# sequencer.net
KiCad netlist of a schematic drawn in EAGLE
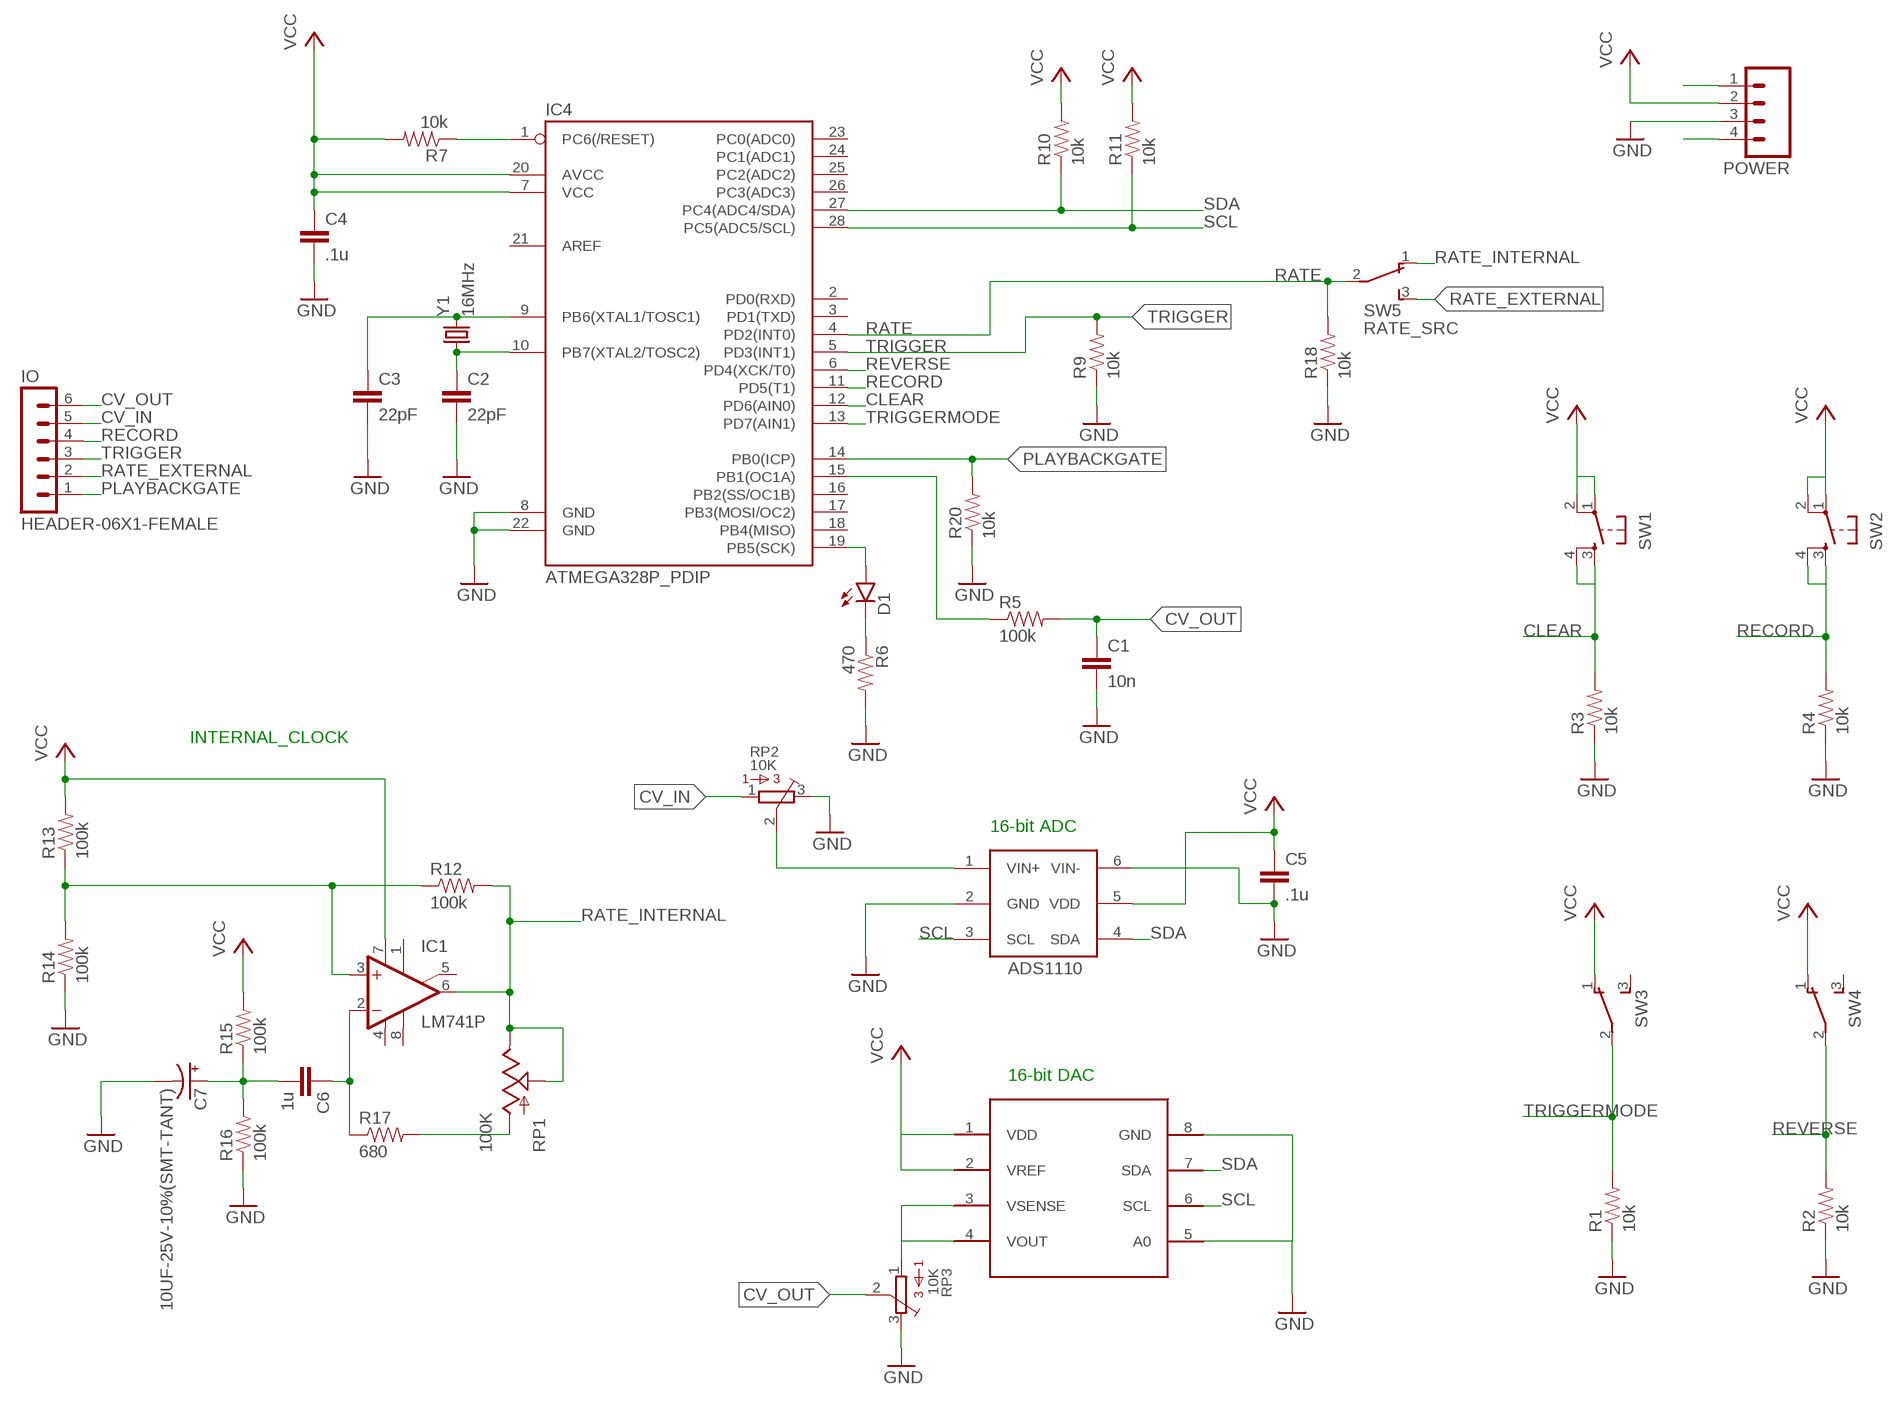
[diagram p0: schematic, sheet 1]

(export (version "E")
  (design (tool "Eeschema 10.0.6"))
  (components
    (comp (ref "C1")
      (value "10n")
      (footprint "eagle-import:1206")
      (libsource (lib "eagle-import") (part "CAP1206"))
    )
    (comp (ref "C2")
      (value "22pF")
      (footprint "eagle-import:1206")
      (libsource (lib "eagle-import") (part "CAP1206"))
    )
    (comp (ref "C3")
      (value "22pF")
      (footprint "eagle-import:1206")
      (libsource (lib "eagle-import") (part "CAP1206"))
    )
    (comp (ref "C4")
      (value ".1u")
      (footprint "eagle-import:1206")
      (libsource (lib "eagle-import") (part "CAP1206"))
    )
    (comp (ref "C5")
      (value ".1u")
      (footprint "eagle-import:1206")
      (libsource (lib "eagle-import") (part "CAP1206"))
    )
    (comp (ref "C6")
      (value "1u")
      (footprint "eagle-import:1206")
      (libsource (lib "eagle-import") (part "CAP1206"))
    )
    (comp (ref "C7")
      (value "10UF-25V-10%(SMT-TANT)")
      (footprint "eagle-import:EIA6032-NOM")
      (libsource (lib "eagle-import") (part "10UF-25V-10%(SMT-TANT)"))
    )
    (comp (ref "D1")
      (value "LED-3MM-NO_SILK")
      (footprint "eagle-import:LED3MM-NS")
      (libsource (lib "eagle-import") (part "LED-3MM-NO_SILK"))
    )
    (comp (ref "IC1")
      (value "LM741P")
      (footprint "eagle-import:DIL08")
      (libsource (lib "eagle-import") (part "741PLM"))
    )
    (comp (ref "IC2")
      (value "ADS1110")
      (footprint "eagle-import:SOT-23-6")
      (libsource (lib "eagle-import") (part "ADS1110"))
    )
    (comp (ref "IC3")
      (value "DAC8571")
      (footprint "eagle-import:8MSOP")
      (libsource (lib "eagle-import") (part "DAC8571"))
    )
    (comp (ref "IC4")
      (value "ATMEGA328P_PDIP")
      (footprint "eagle-import:DIL28-3")
      (libsource (lib "eagle-import") (part "ATMEGA328P_PDIP"))
    )
    (comp (ref "IO")
      (value "HEADER-06X1-FEMALE")
      (footprint "eagle-import:06X1-PTH")
      (libsource (lib "eagle-import") (part "HEADER-06X1?-FEMALE"))
    )
    (comp (ref "POWER")
      (value "M04PTH")
      (footprint "eagle-import:1X04")
      (libsource (lib "eagle-import") (part "M04PTH"))
    )
    (comp (ref "R1")
      (value "10k")
      (footprint "eagle-import:1206")
      (libsource (lib "eagle-import") (part "RESISTOR1206"))
    )
    (comp (ref "R2")
      (value "10k")
      (footprint "eagle-import:1206")
      (libsource (lib "eagle-import") (part "RESISTOR1206"))
    )
    (comp (ref "R3")
      (value "10k")
      (footprint "eagle-import:1206")
      (libsource (lib "eagle-import") (part "RESISTOR1206"))
    )
    (comp (ref "R4")
      (value "10k")
      (footprint "eagle-import:1206")
      (libsource (lib "eagle-import") (part "RESISTOR1206"))
    )
    (comp (ref "R5")
      (value "100k")
      (footprint "eagle-import:1206")
      (libsource (lib "eagle-import") (part "RESISTOR1206"))
    )
    (comp (ref "R6")
      (value "470")
      (footprint "eagle-import:1206")
      (libsource (lib "eagle-import") (part "RESISTOR1206"))
    )
    (comp (ref "R7")
      (value "10k")
      (footprint "eagle-import:1206")
      (libsource (lib "eagle-import") (part "RESISTOR1206"))
    )
    (comp (ref "R9")
      (value "10k")
      (footprint "eagle-import:1206")
      (libsource (lib "eagle-import") (part "RESISTOR1206"))
    )
    (comp (ref "R10")
      (value "10k")
      (footprint "eagle-import:1206")
      (libsource (lib "eagle-import") (part "RESISTOR1206"))
    )
    (comp (ref "R11")
      (value "10k")
      (footprint "eagle-import:1206")
      (libsource (lib "eagle-import") (part "RESISTOR1206"))
    )
    (comp (ref "R12")
      (value "100k")
      (footprint "eagle-import:1206")
      (libsource (lib "eagle-import") (part "RESISTOR1206"))
    )
    (comp (ref "R13")
      (value "100k")
      (footprint "eagle-import:1206")
      (libsource (lib "eagle-import") (part "RESISTOR1206"))
    )
    (comp (ref "R14")
      (value "100k")
      (footprint "eagle-import:1206")
      (libsource (lib "eagle-import") (part "RESISTOR1206"))
    )
    (comp (ref "R15")
      (value "100k")
      (footprint "eagle-import:1206")
      (libsource (lib "eagle-import") (part "RESISTOR1206"))
    )
    (comp (ref "R16")
      (value "100k")
      (footprint "eagle-import:1206")
      (libsource (lib "eagle-import") (part "RESISTOR1206"))
    )
    (comp (ref "R17")
      (value "680")
      (footprint "eagle-import:1206")
      (libsource (lib "eagle-import") (part "RESISTOR1206"))
    )
    (comp (ref "R18")
      (value "10k")
      (footprint "eagle-import:1206")
      (libsource (lib "eagle-import") (part "RESISTOR1206"))
    )
    (comp (ref "R20")
      (value "10k")
      (footprint "eagle-import:1206")
      (libsource (lib "eagle-import") (part "RESISTOR1206"))
    )
    (comp (ref "RP1")
      (value "100K")
      (footprint "eagle-import:ALPS_POT_KIT")
      (libsource (lib "eagle-import") (part "POTALPS-KIT"))
    )
    (comp (ref "RP2")
      (value "10K")
      (footprint "eagle-import:3386P")
      (libsource (lib "eagle-import") (part "3386-P"))
    )
    (comp (ref "RP3")
      (value "10K")
      (footprint "eagle-import:3386P")
      (libsource (lib "eagle-import") (part "3386-P"))
    )
    (comp (ref "SW1")
      (value "TAC_SWITCHPTH")
      (footprint "eagle-import:TACTILE-PTH")
      (libsource (lib "eagle-import") (part "TAC_SWITCHPTH"))
    )
    (comp (ref "SW2")
      (value "TAC_SWITCHPTH")
      (footprint "eagle-import:TACTILE-PTH")
      (libsource (lib "eagle-import") (part "TAC_SWITCHPTH"))
    )
    (comp (ref "SW3")
      (value "TL36YO")
      (footprint "eagle-import:TL3XYO")
      (libsource (lib "eagle-import") (part "TL36YO"))
    )
    (comp (ref "SW4")
      (value "TL36YO")
      (footprint "eagle-import:TL3XYO")
      (libsource (lib "eagle-import") (part "TL36YO"))
    )
    (comp (ref "SW5")
      (value "RATE_SRC")
      (footprint "eagle-import:TL3XYO")
      (libsource (lib "eagle-import") (part "TL36YO"))
    )
    (comp (ref "Y1")
      (value "16MHz")
      (footprint "eagle-import:HC49US")
      (libsource (lib "eagle-import") (part "CRYSTALHC49US"))
    )
  )
  (nets
    (net (code "1") (name "/CLEAR") (class "Default")
      (node (ref "IC4") (pin "12") (pinfunction "PD6(AIN0)_12") (pintype "bidirectional"))
      (node (ref "R3") (pin "2") (pinfunction "2_2") (pintype "passive"))
      (node (ref "SW1") (pin "3") (pinfunction "3_3") (pintype "passive"))
      (node (ref "SW1") (pin "4") (pinfunction "4_4") (pintype "passive"))
    )
    (net (code "2") (name "/RATE") (class "Default")
      (node (ref "IC4") (pin "4") (pinfunction "PD2(INT0)_4") (pintype "bidirectional"))
      (node (ref "R18") (pin "2") (pinfunction "2_2") (pintype "passive"))
      (node (ref "SW5") (pin "2") (pinfunction "P_2") (pintype "passive"))
    )
    (net (code "3") (name "/RATE_INTERNAL") (class "Default")
      (node (ref "IC1") (pin "6") (pinfunction "OUT_6") (pintype "output"))
      (node (ref "R12") (pin "2") (pinfunction "2_2") (pintype "passive"))
      (node (ref "RP1") (pin "P$1") (pinfunction "E_P$1") (pintype "passive"))
      (node (ref "RP1") (pin "P$2") (pinfunction "S_P$2") (pintype "passive"))
      (node (ref "SW5") (pin "1") (pinfunction "O_1") (pintype "passive"))
    )
    (net (code "4") (name "/RECORD") (class "Default")
      (node (ref "IC4") (pin "11") (pinfunction "PD5(T1)_11") (pintype "bidirectional"))
      (node (ref "IO") (pin "4") (pinfunction "4_4") (pintype "passive"))
      (node (ref "R4") (pin "2") (pinfunction "2_2") (pintype "passive"))
      (node (ref "SW2") (pin "3") (pinfunction "3_3") (pintype "passive"))
      (node (ref "SW2") (pin "4") (pinfunction "4_4") (pintype "passive"))
    )
    (net (code "5") (name "/REVERSE") (class "Default")
      (node (ref "IC4") (pin "6") (pinfunction "PD4(XCK/T0)_6") (pintype "bidirectional"))
      (node (ref "R2") (pin "2") (pinfunction "2_2") (pintype "passive"))
      (node (ref "SW4") (pin "2") (pinfunction "P_2") (pintype "passive"))
    )
    (net (code "6") (name "/SCL") (class "Default")
      (node (ref "IC2") (pin "3") (pinfunction "SCL_3") (pintype "bidirectional"))
      (node (ref "IC3") (pin "6") (pinfunction "SCL_6") (pintype "bidirectional"))
      (node (ref "IC4") (pin "28") (pinfunction "PC5(ADC5/SCL)_28") (pintype "bidirectional"))
      (node (ref "R11") (pin "1") (pinfunction "1_1") (pintype "passive"))
    )
    (net (code "7") (name "/SDA") (class "Default")
      (node (ref "IC2") (pin "4") (pinfunction "SDA_4") (pintype "bidirectional"))
      (node (ref "IC3") (pin "7") (pinfunction "SDA_7") (pintype "bidirectional"))
      (node (ref "IC4") (pin "27") (pinfunction "PC4(ADC4/SDA)_27") (pintype "bidirectional"))
      (node (ref "R10") (pin "1") (pinfunction "1_1") (pintype "passive"))
    )
    (net (code "8") (name "/TRIGGERMODE") (class "Default")
      (node (ref "IC4") (pin "13") (pinfunction "PD7(AIN1)_13") (pintype "bidirectional"))
      (node (ref "R1") (pin "2") (pinfunction "2_2") (pintype "passive"))
      (node (ref "SW3") (pin "2") (pinfunction "P_2") (pintype "passive"))
    )
    (net (code "9") (name "/V-") (class "Default")
      (node (ref "IC1") (pin "4") (pinfunction "V-_4") (pintype "power_in"))
    )
    (net (code "10") (name "CV_IN") (class "Default")
      (node (ref "IO") (pin "5") (pinfunction "5_5") (pintype "passive"))
      (node (ref "RP2") (pin "1") (pinfunction "1_1") (pintype "passive"))
    )
    (net (code "11") (name "CV_OUT") (class "Default")
      (node (ref "C1") (pin "1") (pinfunction "1_1") (pintype "passive"))
      (node (ref "IO") (pin "6") (pinfunction "6_6") (pintype "passive"))
      (node (ref "R5") (pin "2") (pinfunction "2_2") (pintype "passive"))
      (node (ref "RP3") (pin "2") (pinfunction "2_2") (pintype "passive"))
    )
    (net (code "12") (name "GND") (class "Default")
      (node (ref "C1") (pin "2") (pinfunction "2_2") (pintype "passive"))
      (node (ref "C2") (pin "2") (pinfunction "2_2") (pintype "passive"))
      (node (ref "C3") (pin "2") (pinfunction "2_2") (pintype "passive"))
      (node (ref "C4") (pin "2") (pinfunction "2_2") (pintype "passive"))
      (node (ref "C5") (pin "2") (pinfunction "2_2") (pintype "passive"))
      (node (ref "C7") (pin "C") (pinfunction "-_C") (pintype "passive"))
      (node (ref "IC2") (pin "2") (pinfunction "GND_2") (pintype "bidirectional"))
      (node (ref "IC2") (pin "6") (pinfunction "VIN-_6") (pintype "bidirectional"))
      (node (ref "IC3") (pin "5") (pinfunction "A0_5") (pintype "bidirectional"))
      (node (ref "IC3") (pin "8") (pinfunction "GND_8") (pintype "bidirectional"))
      (node (ref "IC4") (pin "22") (pinfunction "GND_22") (pintype "bidirectional"))
      (node (ref "IC4") (pin "8") (pinfunction "GND_8") (pintype "bidirectional"))
      (node (ref "POWER") (pin "3") (pinfunction "3_3") (pintype "passive"))
      (node (ref "R1") (pin "1") (pinfunction "1_1") (pintype "passive"))
      (node (ref "R14") (pin "1") (pinfunction "1_1") (pintype "passive"))
      (node (ref "R16") (pin "1") (pinfunction "1_1") (pintype "passive"))
      (node (ref "R18") (pin "1") (pinfunction "1_1") (pintype "passive"))
      (node (ref "R2") (pin "1") (pinfunction "1_1") (pintype "passive"))
      (node (ref "R20") (pin "1") (pinfunction "1_1") (pintype "passive"))
      (node (ref "R3") (pin "1") (pinfunction "1_1") (pintype "passive"))
      (node (ref "R4") (pin "1") (pinfunction "1_1") (pintype "passive"))
      (node (ref "R6") (pin "2") (pinfunction "2_2") (pintype "passive"))
      (node (ref "R9") (pin "1") (pinfunction "1_1") (pintype "passive"))
      (node (ref "RP2") (pin "3") (pinfunction "3_3") (pintype "passive"))
      (node (ref "RP3") (pin "3") (pinfunction "3_3") (pintype "passive"))
    )
    (net (code "13") (name "Net-(C7-+)") (class "Default")
      (node (ref "C6") (pin "2") (pinfunction "2_2") (pintype "passive"))
      (node (ref "C7") (pin "A") (pinfunction "+_A") (pintype "passive"))
      (node (ref "R15") (pin "1") (pinfunction "1_1") (pintype "passive"))
      (node (ref "R16") (pin "2") (pinfunction "2_2") (pintype "passive"))
    )
    (net (code "14") (name "Net-(D1-C)") (class "Default")
      (node (ref "D1") (pin "K") (pinfunction "C_K") (pintype "passive"))
      (node (ref "R6") (pin "1") (pinfunction "1_1") (pintype "passive"))
    )
    (net (code "15") (name "Net-(IC1-+IN)") (class "Default")
      (node (ref "IC1") (pin "3") (pinfunction "+IN_3") (pintype "input"))
      (node (ref "R12") (pin "1") (pinfunction "1_1") (pintype "passive"))
      (node (ref "R13") (pin "1") (pinfunction "1_1") (pintype "passive"))
      (node (ref "R14") (pin "2") (pinfunction "2_2") (pintype "passive"))
    )
    (net (code "16") (name "Net-(IC1--IN)") (class "Default")
      (node (ref "C6") (pin "1") (pinfunction "1_1") (pintype "passive"))
      (node (ref "IC1") (pin "2") (pinfunction "-IN_2") (pintype "input"))
      (node (ref "R17") (pin "1") (pinfunction "1_1") (pintype "passive"))
    )
    (net (code "17") (name "Net-(IC2-VIN+)") (class "Default")
      (node (ref "IC2") (pin "1") (pinfunction "VIN+_1") (pintype "bidirectional"))
      (node (ref "RP2") (pin "2") (pinfunction "2_2") (pintype "passive"))
    )
    (net (code "18") (name "Net-(IC3-VOUT)") (class "Default")
      (node (ref "IC3") (pin "3") (pinfunction "VSENSE_3") (pintype "bidirectional"))
      (node (ref "IC3") (pin "4") (pinfunction "VOUT_4") (pintype "bidirectional"))
      (node (ref "RP3") (pin "1") (pinfunction "1_1") (pintype "passive"))
    )
    (net (code "19") (name "Net-(IC4-PB1(OC1A))") (class "Default")
      (node (ref "IC4") (pin "15") (pinfunction "PB1(OC1A)_15") (pintype "bidirectional"))
      (node (ref "R5") (pin "1") (pinfunction "1_1") (pintype "passive"))
    )
    (net (code "20") (name "Net-(IC4-PB5(SCK))") (class "Default")
      (node (ref "D1") (pin "A") (pinfunction "A_A") (pintype "passive"))
      (node (ref "IC4") (pin "19") (pinfunction "PB5(SCK)_19") (pintype "bidirectional"))
    )
    (net (code "21") (name "Net-(IC4-PB6(XTAL1{slash}TOSC1))") (class "Default")
      (node (ref "C3") (pin "1") (pinfunction "1_1") (pintype "passive"))
      (node (ref "IC4") (pin "9") (pinfunction "PB6(XTAL1/TOSC1)_9") (pintype "bidirectional"))
      (node (ref "Y1") (pin "2") (pinfunction "2_2") (pintype "passive"))
    )
    (net (code "22") (name "Net-(IC4-PB7(XTAL2{slash}TOSC2))") (class "Default")
      (node (ref "C2") (pin "1") (pinfunction "1_1") (pintype "passive"))
      (node (ref "IC4") (pin "10") (pinfunction "PB7(XTAL2/TOSC2)_10") (pintype "bidirectional"))
      (node (ref "Y1") (pin "1") (pinfunction "1_1") (pintype "passive"))
    )
    (net (code "23") (name "Net-(IC4-PC6({slash}RESET))") (class "Default")
      (node (ref "IC4") (pin "1") (pinfunction "PC6(/RESET)_1") (pintype "bidirectional"))
      (node (ref "R7") (pin "1") (pinfunction "1_1") (pintype "passive"))
    )
    (net (code "24") (name "Net-(RP1-A)") (class "Default")
      (node (ref "R17") (pin "2") (pinfunction "2_2") (pintype "passive"))
      (node (ref "RP1") (pin "P$3") (pinfunction "A_P$3") (pintype "passive"))
    )
    (net (code "25") (name "PLAYBACKGATE") (class "Default")
      (node (ref "IC4") (pin "14") (pinfunction "PB0(ICP)_14") (pintype "bidirectional"))
      (node (ref "IO") (pin "1") (pinfunction "1_1") (pintype "passive"))
      (node (ref "R20") (pin "2") (pinfunction "2_2") (pintype "passive"))
    )
    (net (code "26") (name "RATE_EXTERNAL") (class "Default")
      (node (ref "IO") (pin "2") (pinfunction "2_2") (pintype "passive"))
      (node (ref "SW5") (pin "3") (pinfunction "S_3") (pintype "passive"))
    )
    (net (code "27") (name "TRIGGER") (class "Default")
      (node (ref "IC4") (pin "5") (pinfunction "PD3(INT1)_5") (pintype "bidirectional"))
      (node (ref "IO") (pin "3") (pinfunction "3_3") (pintype "passive"))
      (node (ref "R9") (pin "2") (pinfunction "2_2") (pintype "passive"))
    )
    (net (code "28") (name "VCC") (class "Default")
      (node (ref "C4") (pin "1") (pinfunction "1_1") (pintype "passive"))
      (node (ref "C5") (pin "1") (pinfunction "1_1") (pintype "passive"))
      (node (ref "IC1") (pin "7") (pinfunction "V+_7") (pintype "power_in"))
      (node (ref "IC2") (pin "5") (pinfunction "VDD_5") (pintype "bidirectional"))
      (node (ref "IC3") (pin "1") (pinfunction "VDD_1") (pintype "bidirectional"))
      (node (ref "IC3") (pin "2") (pinfunction "VREF_2") (pintype "bidirectional"))
      (node (ref "IC4") (pin "20") (pinfunction "AVCC_20") (pintype "bidirectional"))
      (node (ref "IC4") (pin "7") (pinfunction "VCC_7") (pintype "bidirectional"))
      (node (ref "POWER") (pin "2") (pinfunction "2_2") (pintype "passive"))
      (node (ref "R10") (pin "2") (pinfunction "2_2") (pintype "passive"))
      (node (ref "R11") (pin "2") (pinfunction "2_2") (pintype "passive"))
      (node (ref "R13") (pin "2") (pinfunction "2_2") (pintype "passive"))
      (node (ref "R15") (pin "2") (pinfunction "2_2") (pintype "passive"))
      (node (ref "R7") (pin "2") (pinfunction "2_2") (pintype "passive"))
      (node (ref "SW1") (pin "1") (pinfunction "1_1") (pintype "passive"))
      (node (ref "SW1") (pin "2") (pinfunction "2_2") (pintype "passive"))
      (node (ref "SW2") (pin "1") (pinfunction "1_1") (pintype "passive"))
      (node (ref "SW2") (pin "2") (pinfunction "2_2") (pintype "passive"))
      (node (ref "SW3") (pin "1") (pinfunction "O_1") (pintype "passive"))
      (node (ref "SW4") (pin "1") (pinfunction "O_1") (pintype "passive"))
    )
    (net (code "29") (name "unconnected-(IC1-ON1-Pad1)") (class "Default")
      (node (ref "IC1") (pin "1") (pinfunction "ON1_1") (pintype "passive"))
    )
    (net (code "30") (name "unconnected-(IC1-ON2-Pad5)") (class "Default")
      (node (ref "IC1") (pin "5") (pinfunction "ON2_5") (pintype "passive"))
    )
    (net (code "31") (name "unconnected-(IC1-OPT-Pad8)") (class "Default")
      (node (ref "IC1") (pin "8") (pinfunction "OPT_8") (pintype "passive"))
    )
    (net (code "32") (name "unconnected-(IC4-AREF-Pad21)") (class "Default")
      (node (ref "IC4") (pin "21") (pinfunction "AREF_21") (pintype "bidirectional"))
    )
    (net (code "33") (name "unconnected-(IC4-PB2(SS{slash}OC1B)-Pad16)") (class "Default")
      (node (ref "IC4") (pin "16") (pinfunction "PB2(SS/OC1B)_16") (pintype "bidirectional"))
    )
    (net (code "34") (name "unconnected-(IC4-PB3(MOSI{slash}OC2)-Pad17)") (class "Default")
      (node (ref "IC4") (pin "17") (pinfunction "PB3(MOSI/OC2)_17") (pintype "bidirectional"))
    )
    (net (code "35") (name "unconnected-(IC4-PB4(MISO)-Pad18)") (class "Default")
      (node (ref "IC4") (pin "18") (pinfunction "PB4(MISO)_18") (pintype "bidirectional"))
    )
    (net (code "36") (name "unconnected-(IC4-PC0(ADC0)-Pad23)") (class "Default")
      (node (ref "IC4") (pin "23") (pinfunction "PC0(ADC0)_23") (pintype "bidirectional"))
    )
    (net (code "37") (name "unconnected-(IC4-PC1(ADC1)-Pad24)") (class "Default")
      (node (ref "IC4") (pin "24") (pinfunction "PC1(ADC1)_24") (pintype "bidirectional"))
    )
    (net (code "38") (name "unconnected-(IC4-PC2(ADC2)-Pad25)") (class "Default")
      (node (ref "IC4") (pin "25") (pinfunction "PC2(ADC2)_25") (pintype "bidirectional"))
    )
    (net (code "39") (name "unconnected-(IC4-PC3(ADC3)-Pad26)") (class "Default")
      (node (ref "IC4") (pin "26") (pinfunction "PC3(ADC3)_26") (pintype "bidirectional"))
    )
    (net (code "40") (name "unconnected-(IC4-PD0(RXD)-Pad2)") (class "Default")
      (node (ref "IC4") (pin "2") (pinfunction "PD0(RXD)_2") (pintype "bidirectional"))
    )
    (net (code "41") (name "unconnected-(IC4-PD1(TXD)-Pad3)") (class "Default")
      (node (ref "IC4") (pin "3") (pinfunction "PD1(TXD)_3") (pintype "bidirectional"))
    )
    (net (code "42") (name "unconnected-(POWER-Pad1)") (class "Default")
      (node (ref "POWER") (pin "1") (pinfunction "1_1") (pintype "passive"))
    )
    (net (code "43") (name "unconnected-(POWER-Pad4)") (class "Default")
      (node (ref "POWER") (pin "4") (pinfunction "4_4") (pintype "passive"))
    )
    (net (code "44") (name "unconnected-(SW3-S-Pad3)") (class "Default")
      (node (ref "SW3") (pin "3") (pinfunction "S_3") (pintype "passive"))
    )
    (net (code "45") (name "unconnected-(SW4-S-Pad3)") (class "Default")
      (node (ref "SW4") (pin "3") (pinfunction "S_3") (pintype "passive"))
    )
  )
)
